# Prox2.net
KiCad netlist of a schematic drawn in Altium Designer
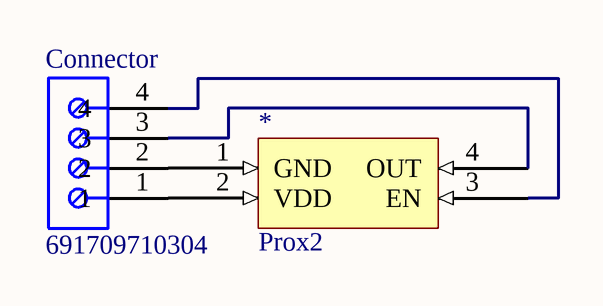
[diagram p0: Prox2.SchDoc]

(export (version "E")
  (design (tool "Eeschema 10.0.6"))
  (components
    (comp (ref "*")
      (value "Prox2")
      (footprint "PCBComponent_1")
      (libsource (lib "F24-250-C2") (part "Component_1"))
    )
    (comp (ref "Connector")
      (value "691709710304")
      (footprint "691709710304")
      (fields (field (name "VOLTAGE") "300V"))
      (libsource (lib "Altium Content Vault") (part "TBL - 1R - 04P - Screw"))
    )
  )
  (nets
    (net (code "1") (name "Net-(*-EN)") (class "Default")
      (node (ref "*") (pin "3") (pinfunction "EN_3") (pintype "input"))
      (node (ref "Connector") (pin "4") (pinfunction "4_4") (pintype "passive"))
    )
    (net (code "2") (name "Net-(*-GND)") (class "Default")
      (node (ref "*") (pin "1") (pinfunction "GND_1") (pintype "input"))
      (node (ref "Connector") (pin "2") (pinfunction "2_2") (pintype "passive"))
    )
    (net (code "3") (name "Net-(*-OUT)") (class "Default")
      (node (ref "*") (pin "4") (pinfunction "OUT_4") (pintype "input"))
      (node (ref "Connector") (pin "3") (pinfunction "3_3") (pintype "passive"))
    )
    (net (code "4") (name "Net-(*-VDD)") (class "Default")
      (node (ref "*") (pin "2") (pinfunction "VDD_2") (pintype "input"))
      (node (ref "Connector") (pin "1") (pinfunction "1_1") (pintype "passive"))
    )
  )
)
